# TouchConnector.net
KiCad netlist of a schematic drawn in EAGLE
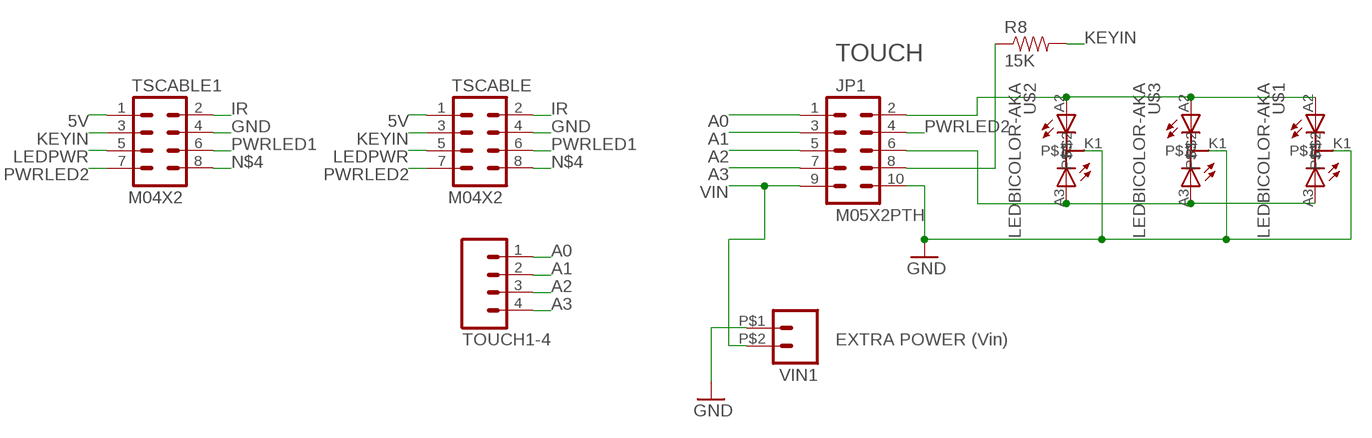
[diagram p0: schematic, sheet 1]

(export (version "E")
  (design (tool "Eeschema 10.0.6"))
  (components
    (comp (ref "JP1")
      (value "M05X2PTH")
      (footprint "eagle-import:AVR_ICSP")
      (libsource (lib "eagle-import") (part "M05X2PTH"))
    )
    (comp (ref "R8")
      (value "15K")
      (footprint "eagle-import:0603-RES")
      (libsource (lib "eagle-import") (part "RESISTOR0603-RES"))
    )
    (comp (ref "TOUCH1-4")
      (value "M04PTH")
      (footprint "eagle-import:1X04")
      (libsource (lib "eagle-import") (part "M04PTH"))
    )
    (comp (ref "TSCABLE")
      (value "M04X2")
      (footprint "eagle-import:2X4")
      (libsource (lib "eagle-import") (part "M04X2"))
    )
    (comp (ref "TSCABLE1")
      (value "M04X2")
      (footprint "eagle-import:2X4")
      (libsource (lib "eagle-import") (part "M04X2"))
    )
    (comp (ref "U$1")
      (value "LEDBICOLOR-AKA")
      (footprint "eagle-import:LED5MM-BICOLOR")
      (libsource (lib "eagle-import") (part "LEDBICOLOR-AKA"))
    )
    (comp (ref "U$2")
      (value "LEDBICOLOR-AKA")
      (footprint "eagle-import:LED5MM-BICOLOR")
      (libsource (lib "eagle-import") (part "LEDBICOLOR-AKA"))
    )
    (comp (ref "U$3")
      (value "LEDBICOLOR-AKA")
      (footprint "eagle-import:LED5MM-BICOLOR")
      (libsource (lib "eagle-import") (part "LEDBICOLOR-AKA"))
    )
    (comp (ref "VIN1")
      (value "M02PTH2")
      (footprint "eagle-import:1X02_BIG")
      (libsource (lib "eagle-import") (part "M02PTH2"))
    )
  )
  (nets
    (net (code "1") (name "/5V") (class "Default")
      (node (ref "TSCABLE") (pin "1") (pinfunction "1_1") (pintype "passive"))
      (node (ref "TSCABLE1") (pin "1") (pinfunction "1_1") (pintype "passive"))
    )
    (net (code "2") (name "/A0") (class "Default")
      (node (ref "JP1") (pin "1") (pinfunction "1_1") (pintype "passive"))
      (node (ref "TOUCH1-4") (pin "1") (pinfunction "1_1") (pintype "passive"))
    )
    (net (code "3") (name "/A1") (class "Default")
      (node (ref "JP1") (pin "3") (pinfunction "3_3") (pintype "passive"))
      (node (ref "TOUCH1-4") (pin "2") (pinfunction "2_2") (pintype "passive"))
    )
    (net (code "4") (name "/A2") (class "Default")
      (node (ref "JP1") (pin "5") (pinfunction "5_5") (pintype "passive"))
      (node (ref "TOUCH1-4") (pin "3") (pinfunction "3_3") (pintype "passive"))
    )
    (net (code "5") (name "/A3") (class "Default")
      (node (ref "JP1") (pin "7") (pinfunction "7_7") (pintype "passive"))
      (node (ref "TOUCH1-4") (pin "4") (pinfunction "4_4") (pintype "passive"))
    )
    (net (code "6") (name "/IR") (class "Default")
      (node (ref "TSCABLE") (pin "2") (pinfunction "2_2") (pintype "passive"))
      (node (ref "TSCABLE1") (pin "2") (pinfunction "2_2") (pintype "passive"))
    )
    (net (code "7") (name "/KEYIN") (class "Default")
      (node (ref "R8") (pin "2") (pinfunction "2_2") (pintype "passive"))
      (node (ref "TSCABLE") (pin "3") (pinfunction "3_3") (pintype "passive"))
      (node (ref "TSCABLE1") (pin "3") (pinfunction "3_3") (pintype "passive"))
    )
    (net (code "8") (name "/LEDPWR") (class "Default")
      (node (ref "TSCABLE") (pin "5") (pinfunction "5_5") (pintype "passive"))
      (node (ref "TSCABLE1") (pin "5") (pinfunction "5_5") (pintype "passive"))
    )
    (net (code "9") (name "/N$4") (class "Default")
      (node (ref "TSCABLE") (pin "8") (pinfunction "8_8") (pintype "passive"))
      (node (ref "TSCABLE1") (pin "8") (pinfunction "8_8") (pintype "passive"))
    )
    (net (code "10") (name "/PWRLED1") (class "Default")
      (node (ref "TSCABLE") (pin "6") (pinfunction "6_6") (pintype "passive"))
      (node (ref "TSCABLE1") (pin "6") (pinfunction "6_6") (pintype "passive"))
    )
    (net (code "11") (name "/PWRLED2") (class "Default")
      (node (ref "JP1") (pin "4") (pinfunction "4_4") (pintype "passive"))
      (node (ref "TSCABLE") (pin "7") (pinfunction "7_7") (pintype "passive"))
      (node (ref "TSCABLE1") (pin "7") (pinfunction "7_7") (pintype "passive"))
    )
    (net (code "12") (name "/VIN") (class "Default")
      (node (ref "JP1") (pin "9") (pinfunction "9_9") (pintype "passive"))
      (node (ref "VIN1") (pin "P$2") (pinfunction "2_P$2") (pintype "passive"))
    )
    (net (code "13") (name "GND") (class "Default")
      (node (ref "JP1") (pin "10") (pinfunction "10_10") (pintype "passive"))
      (node (ref "TSCABLE") (pin "4") (pinfunction "4_4") (pintype "passive"))
      (node (ref "TSCABLE1") (pin "4") (pinfunction "4_4") (pintype "passive"))
      (node (ref "U$1") (pin "K1") (pinfunction "P$1_K1") (pintype "bidirectional"))
      (node (ref "U$2") (pin "K1") (pinfunction "P$1_K1") (pintype "bidirectional"))
      (node (ref "U$3") (pin "K1") (pinfunction "P$1_K1") (pintype "bidirectional"))
      (node (ref "VIN1") (pin "P$1") (pinfunction "1_P$1") (pintype "passive"))
    )
    (net (code "14") (name "Net-(JP1-Pad8)") (class "Default")
      (node (ref "JP1") (pin "8") (pinfunction "8_8") (pintype "passive"))
      (node (ref "R8") (pin "1") (pinfunction "1_1") (pintype "passive"))
    )
    (net (code "15") (name "Net-(U$1-P$2)") (class "Default")
      (node (ref "JP1") (pin "2") (pinfunction "2_2") (pintype "passive"))
      (node (ref "U$1") (pin "A2") (pinfunction "P$2_A2") (pintype "bidirectional"))
      (node (ref "U$2") (pin "A2") (pinfunction "P$2_A2") (pintype "bidirectional"))
      (node (ref "U$3") (pin "A2") (pinfunction "P$2_A2") (pintype "bidirectional"))
    )
    (net (code "16") (name "Net-(U$1-P$3)") (class "Default")
      (node (ref "JP1") (pin "6") (pinfunction "6_6") (pintype "passive"))
      (node (ref "U$1") (pin "A3") (pinfunction "P$3_A3") (pintype "bidirectional"))
      (node (ref "U$2") (pin "A3") (pinfunction "P$3_A3") (pintype "bidirectional"))
      (node (ref "U$3") (pin "A3") (pinfunction "P$3_A3") (pintype "bidirectional"))
    )
  )
)
